# mainboard.net
KiCad netlist of a schematic drawn in EAGLE
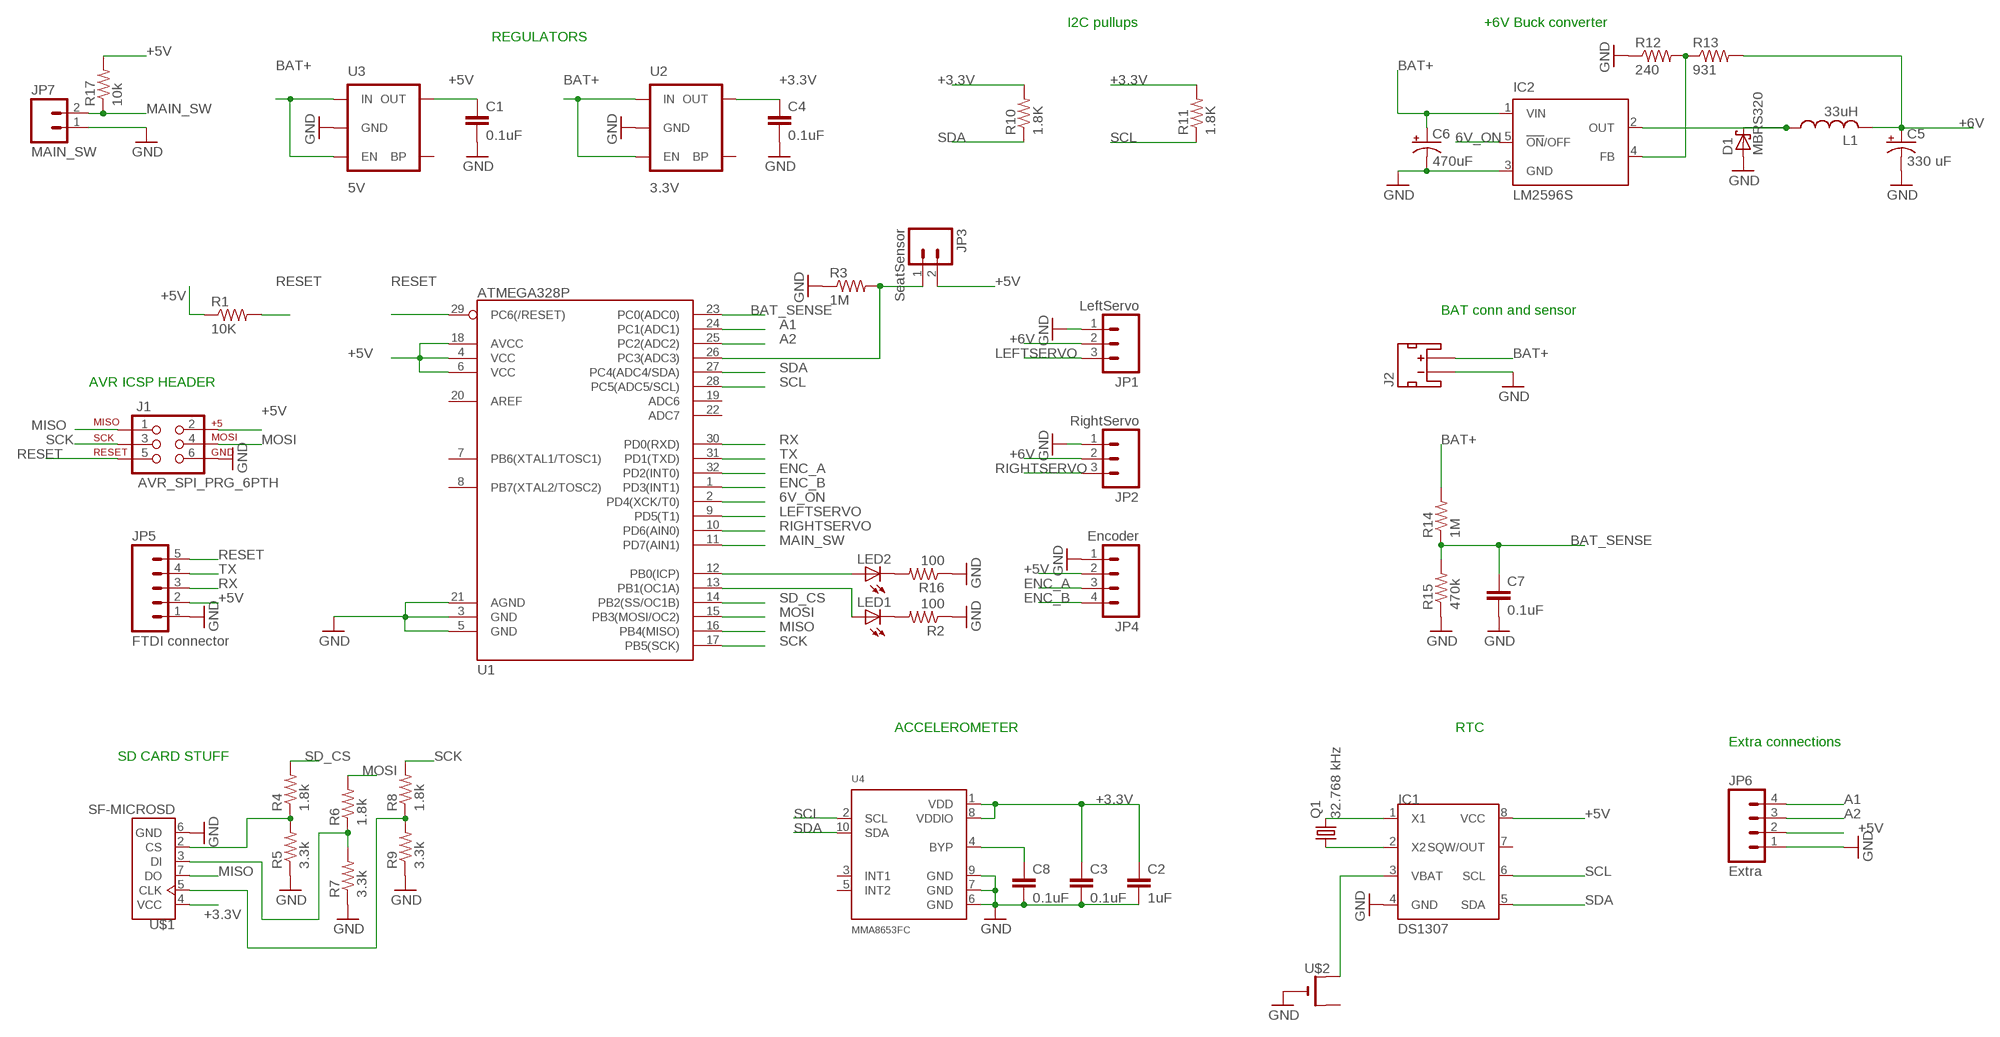
[diagram p0: schematic, sheet 1]

(export (version "E")
  (design (tool "Eeschema 10.0.6"))
  (components
    (comp (ref "C1")
      (value "0.1uF")
      (footprint "eagle-import:0603-CAP")
      (libsource (lib "eagle-import") (part "CAP0603-CAP"))
    )
    (comp (ref "C2")
      (value "1uF")
      (footprint "eagle-import:0603-CAP")
      (libsource (lib "eagle-import") (part "CAP0603-CAP"))
    )
    (comp (ref "C3")
      (value "0.1uF")
      (footprint "eagle-import:0603-CAP")
      (libsource (lib "eagle-import") (part "CAP0603-CAP"))
    )
    (comp (ref "C4")
      (value "0.1uF")
      (footprint "eagle-import:0603-CAP")
      (libsource (lib "eagle-import") (part "CAP0603-CAP"))
    )
    (comp (ref "C5")
      (value "330 uF")
      (footprint "eagle-import:PANASONIC_E")
      (libsource (lib "eagle-import") (part "CAP_POLE"))
    )
    (comp (ref "C6")
      (value "470uF")
      (footprint "eagle-import:PANASONIC_G")
      (libsource (lib "eagle-import") (part "CAP_POLG"))
    )
    (comp (ref "C7")
      (value "0.1uF")
      (footprint "eagle-import:0603-CAP")
      (libsource (lib "eagle-import") (part "CAP0603-CAP"))
    )
    (comp (ref "C8")
      (value "0.1uF")
      (footprint "eagle-import:0603-CAP")
      (libsource (lib "eagle-import") (part "CAP0603-CAP"))
    )
    (comp (ref "D1")
      (value "MBRS320")
      (footprint "eagle-import:SMC")
      (libsource (lib "eagle-import") (part "SCHOTTKY-DIODESMC"))
    )
    (comp (ref "IC1")
      (value "DS1307")
      (footprint "eagle-import:SOIC-8")
      (libsource (lib "eagle-import") (part "DS1307"))
    )
    (comp (ref "IC2")
      (value "LM2596S")
      (footprint "eagle-import:TO263-5")
      (fields (field (name "MF") "NATIONAL SEMICONDUCTOR") (field (name "MPN") "LM2596S-ADJ/NOPB"))
      (libsource (lib "eagle-import") (part "LM2596S"))
    )
    (comp (ref "J1")
      (value "AVR_SPI_PRG_6PTH")
      (footprint "eagle-import:2X3")
      (libsource (lib "eagle-import") (part "AVR_SPI_PRG_6PTH"))
    )
    (comp (ref "J2")
      (value "JST_2MM_MALE")
      (footprint "eagle-import:JST-2-SMD")
      (libsource (lib "eagle-import") (part "JST_2MM_MALE"))
    )
    (comp (ref "JP1")
      (value "LeftServo")
      (footprint "eagle-import:1X03")
      (libsource (lib "eagle-import") (part "M03PTH"))
    )
    (comp (ref "JP2")
      (value "RightServo")
      (footprint "eagle-import:1X03")
      (libsource (lib "eagle-import") (part "M03PTH"))
    )
    (comp (ref "JP3")
      (value "SeatSensor")
      (footprint "eagle-import:1X02")
      (libsource (lib "eagle-import") (part "M02PTH"))
    )
    (comp (ref "JP4")
      (value "Encoder")
      (footprint "eagle-import:1X04")
      (libsource (lib "eagle-import") (part "M04PTH"))
    )
    (comp (ref "JP5")
      (value "FTDI connector")
      (footprint "eagle-import:1X05")
      (libsource (lib "eagle-import") (part "M05PTH"))
    )
    (comp (ref "JP6")
      (value "Extra")
      (footprint "eagle-import:1X04")
      (libsource (lib "eagle-import") (part "M04PTH"))
    )
    (comp (ref "JP7")
      (value "MAIN_SW")
      (footprint "eagle-import:1X02")
      (libsource (lib "eagle-import") (part "M02PTH"))
    )
    (comp (ref "L1")
      (value "33uH")
      (footprint "eagle-import:SRR1280")
      (libsource (lib "eagle-import") (part "L-SRR1280"))
    )
    (comp (ref "LED1")
      (value "LED1206")
      (footprint "eagle-import:LED-1206")
      (libsource (lib "eagle-import") (part "LED1206"))
    )
    (comp (ref "LED2")
      (value "LED1206")
      (footprint "eagle-import:LED-1206")
      (libsource (lib "eagle-import") (part "LED1206"))
    )
    (comp (ref "Q1")
      (value "32.768 kHz")
      (footprint "eagle-import:TC38H")
      (libsource (lib "eagle-import") (part "CRYSTALTC38H"))
    )
    (comp (ref "R1")
      (value "10K")
      (footprint "eagle-import:0603-RES")
      (libsource (lib "eagle-import") (part "RESISTOR0603-RES"))
    )
    (comp (ref "R2")
      (value "100")
      (footprint "eagle-import:0603-RES")
      (libsource (lib "eagle-import") (part "RESISTOR0603-RES"))
    )
    (comp (ref "R3")
      (value "1M")
      (footprint "eagle-import:0603-RES")
      (libsource (lib "eagle-import") (part "RESISTOR0603-RES"))
    )
    (comp (ref "R4")
      (value "1.8k")
      (footprint "eagle-import:0603-RES")
      (libsource (lib "eagle-import") (part "RESISTOR0603"))
    )
    (comp (ref "R5")
      (value "3.3k")
      (footprint "eagle-import:0603-RES")
      (libsource (lib "eagle-import") (part "RESISTOR0603"))
    )
    (comp (ref "R6")
      (value "1.8k")
      (footprint "eagle-import:0603-RES")
      (libsource (lib "eagle-import") (part "RESISTOR0603"))
    )
    (comp (ref "R7")
      (value "3.3k")
      (footprint "eagle-import:0603-RES")
      (libsource (lib "eagle-import") (part "RESISTOR0603"))
    )
    (comp (ref "R8")
      (value "1.8k")
      (footprint "eagle-import:0603-RES")
      (libsource (lib "eagle-import") (part "RESISTOR0603"))
    )
    (comp (ref "R9")
      (value "3.3k")
      (footprint "eagle-import:0603-RES")
      (libsource (lib "eagle-import") (part "RESISTOR0603"))
    )
    (comp (ref "R10")
      (value "1.8K")
      (footprint "eagle-import:0603-RES")
      (libsource (lib "eagle-import") (part "RESISTOR0603-RES"))
    )
    (comp (ref "R11")
      (value "1.8K")
      (footprint "eagle-import:0603-RES")
      (libsource (lib "eagle-import") (part "RESISTOR0603-RES"))
    )
    (comp (ref "R12")
      (value "240")
      (footprint "eagle-import:0603-RES")
      (libsource (lib "eagle-import") (part "RESISTOR0603"))
    )
    (comp (ref "R13")
      (value "931")
      (footprint "eagle-import:0603-RES")
      (libsource (lib "eagle-import") (part "RESISTOR0603"))
    )
    (comp (ref "R14")
      (value "1M")
      (footprint "eagle-import:0603-RES")
      (libsource (lib "eagle-import") (part "RESISTOR0603"))
    )
    (comp (ref "R15")
      (value "470k")
      (footprint "eagle-import:0603-RES")
      (libsource (lib "eagle-import") (part "RESISTOR0603"))
    )
    (comp (ref "R16")
      (value "100")
      (footprint "eagle-import:0603-RES")
      (libsource (lib "eagle-import") (part "RESISTOR0603"))
    )
    (comp (ref "R17")
      (value "10k")
      (footprint "eagle-import:0603-RES")
      (libsource (lib "eagle-import") (part "RESISTOR0603"))
    )
    (comp (ref "U$1")
      (value "SF-MICROSD")
      (footprint "eagle-import:MICROSD")
      (libsource (lib "eagle-import") (part "SF-MICROSD"))
    )
    (comp (ref "U$2")
      (value "CR1220SMT")
      (footprint "eagle-import:CR1220-SMD")
      (libsource (lib "eagle-import") (part "CR1220SMT"))
    )
    (comp (ref "U1")
      (value "ATMEGA328P")
      (footprint "eagle-import:TQFP32-08")
      (libsource (lib "eagle-import") (part "ATMEGA328_SMT"))
    )
    (comp (ref "U2")
      (value "3.3V")
      (footprint "eagle-import:SOT23-5")
      (libsource (lib "eagle-import") (part "MIC52053.3V"))
    )
    (comp (ref "U3")
      (value "5V")
      (footprint "eagle-import:SOT23-5")
      (libsource (lib "eagle-import") (part "MIC52055V"))
    )
    (comp (ref "U4")
      (value "MMA8653FC")
      (footprint "eagle-import:DFN10-2X2")
      (libsource (lib "eagle-import") (part "MMA8653FC"))
    )
  )
  (nets
    (net (code "1") (name "/+3.3V") (class "Default")
      (node (ref "C2") (pin "1") (pinfunction "1_1") (pintype "passive"))
      (node (ref "C3") (pin "1") (pinfunction "1_1") (pintype "passive"))
      (node (ref "C4") (pin "1") (pinfunction "1_1") (pintype "passive"))
      (node (ref "R10") (pin "2") (pinfunction "2_2") (pintype "passive"))
      (node (ref "R11") (pin "2") (pinfunction "2_2") (pintype "passive"))
      (node (ref "U$1") (pin "4") (pinfunction "VCC_4") (pintype "passive"))
      (node (ref "U2") (pin "5") (pinfunction "OUT_5") (pintype "passive"))
      (node (ref "U4") (pin "1") (pinfunction "VDD_1") (pintype "bidirectional"))
      (node (ref "U4") (pin "8") (pinfunction "VDDIO_8") (pintype "bidirectional"))
    )
    (net (code "2") (name "/+5V") (class "Default")
      (node (ref "C1") (pin "1") (pinfunction "1_1") (pintype "passive"))
      (node (ref "IC1") (pin "8") (pinfunction "VCC_8") (pintype "power_in"))
      (node (ref "J1") (pin "2") (pinfunction "2_2") (pintype "passive"))
      (node (ref "JP3") (pin "2") (pinfunction "2_2") (pintype "passive"))
      (node (ref "JP4") (pin "2") (pinfunction "2_2") (pintype "passive"))
      (node (ref "JP5") (pin "2") (pinfunction "2_2") (pintype "passive"))
      (node (ref "JP6") (pin "2") (pinfunction "2_2") (pintype "passive"))
      (node (ref "R1") (pin "1") (pinfunction "1_1") (pintype "passive"))
      (node (ref "R17") (pin "2") (pinfunction "2_2") (pintype "passive"))
      (node (ref "U1") (pin "18") (pinfunction "AVCC_18") (pintype "bidirectional"))
      (node (ref "U1") (pin "4") (pinfunction "VCC_4") (pintype "bidirectional"))
      (node (ref "U1") (pin "6") (pinfunction "VCC_6") (pintype "bidirectional"))
      (node (ref "U3") (pin "5") (pinfunction "OUT_5") (pintype "passive"))
    )
    (net (code "3") (name "/+6V") (class "Default")
      (node (ref "C5") (pin "+") (pinfunction "+_+") (pintype "passive"))
      (node (ref "JP1") (pin "2") (pinfunction "2_2") (pintype "passive"))
      (node (ref "JP2") (pin "2") (pinfunction "2_2") (pintype "passive"))
      (node (ref "L1") (pin "2") (pinfunction "2_2") (pintype "passive"))
      (node (ref "R13") (pin "2") (pinfunction "2_2") (pintype "passive"))
    )
    (net (code "4") (name "/6V_ON") (class "Default")
      (node (ref "IC2") (pin "5") (pinfunction "~{ON}/OFF_5") (pintype "input"))
      (node (ref "U1") (pin "2") (pinfunction "PD4(XCK/T0)_2") (pintype "bidirectional"))
    )
    (net (code "5") (name "/A1") (class "Default")
      (node (ref "JP6") (pin "4") (pinfunction "4_4") (pintype "passive"))
      (node (ref "U1") (pin "24") (pinfunction "PC1(ADC1)_24") (pintype "bidirectional"))
    )
    (net (code "6") (name "/A2") (class "Default")
      (node (ref "JP6") (pin "3") (pinfunction "3_3") (pintype "passive"))
      (node (ref "U1") (pin "25") (pinfunction "PC2(ADC2)_25") (pintype "bidirectional"))
    )
    (net (code "7") (name "/BAT+") (class "Default")
      (node (ref "C6") (pin "+") (pinfunction "+_+") (pintype "passive"))
      (node (ref "IC2") (pin "1") (pinfunction "VIN_1") (pintype "input"))
      (node (ref "J2") (pin "2") (pinfunction "+_2") (pintype "bidirectional"))
      (node (ref "R14") (pin "2") (pinfunction "2_2") (pintype "passive"))
      (node (ref "U2") (pin "1") (pinfunction "IN_1") (pintype "input"))
      (node (ref "U2") (pin "3") (pinfunction "EN_3") (pintype "input"))
      (node (ref "U3") (pin "1") (pinfunction "IN_1") (pintype "input"))
      (node (ref "U3") (pin "3") (pinfunction "EN_3") (pintype "input"))
    )
    (net (code "8") (name "/BAT_SENSE") (class "Default")
      (node (ref "C7") (pin "1") (pinfunction "1_1") (pintype "passive"))
      (node (ref "R14") (pin "1") (pinfunction "1_1") (pintype "passive"))
      (node (ref "R15") (pin "2") (pinfunction "2_2") (pintype "passive"))
      (node (ref "U1") (pin "23") (pinfunction "PC0(ADC0)_23") (pintype "bidirectional"))
    )
    (net (code "9") (name "/ENC_A") (class "Default")
      (node (ref "JP4") (pin "3") (pinfunction "3_3") (pintype "passive"))
      (node (ref "U1") (pin "32") (pinfunction "PD2(INT0)_32") (pintype "bidirectional"))
    )
    (net (code "10") (name "/ENC_B") (class "Default")
      (node (ref "JP4") (pin "4") (pinfunction "4_4") (pintype "passive"))
      (node (ref "U1") (pin "1") (pinfunction "PD3(INT1)_1") (pintype "bidirectional"))
    )
    (net (code "11") (name "/LEFTSERVO") (class "Default")
      (node (ref "JP1") (pin "3") (pinfunction "3_3") (pintype "passive"))
      (node (ref "U1") (pin "9") (pinfunction "PD5(T1)_9") (pintype "bidirectional"))
    )
    (net (code "12") (name "/MAIN_SW") (class "Default")
      (node (ref "JP7") (pin "2") (pinfunction "2_2") (pintype "passive"))
      (node (ref "R17") (pin "1") (pinfunction "1_1") (pintype "passive"))
      (node (ref "U1") (pin "11") (pinfunction "PD7(AIN1)_11") (pintype "bidirectional"))
    )
    (net (code "13") (name "/MISO") (class "Default")
      (node (ref "J1") (pin "1") (pinfunction "1_1") (pintype "passive"))
      (node (ref "U$1") (pin "7") (pinfunction "DO_7") (pintype "bidirectional"))
      (node (ref "U1") (pin "16") (pinfunction "PB4(MISO)_16") (pintype "bidirectional"))
    )
    (net (code "14") (name "/MOSI") (class "Default")
      (node (ref "J1") (pin "4") (pinfunction "4_4") (pintype "passive"))
      (node (ref "R6") (pin "2") (pinfunction "2_2") (pintype "passive"))
      (node (ref "U1") (pin "15") (pinfunction "PB3(MOSI/OC2)_15") (pintype "bidirectional"))
    )
    (net (code "15") (name "/RESET") (class "Default")
      (node (ref "J1") (pin "5") (pinfunction "5_5") (pintype "passive"))
      (node (ref "JP5") (pin "5") (pinfunction "5_5") (pintype "passive"))
      (node (ref "R1") (pin "2") (pinfunction "2_2") (pintype "passive"))
      (node (ref "U1") (pin "29") (pinfunction "PC6(/RESET)_29") (pintype "bidirectional"))
    )
    (net (code "16") (name "/RIGHTSERVO") (class "Default")
      (node (ref "JP2") (pin "3") (pinfunction "3_3") (pintype "passive"))
      (node (ref "U1") (pin "10") (pinfunction "PD6(AIN0)_10") (pintype "bidirectional"))
    )
    (net (code "17") (name "/RX") (class "Default")
      (node (ref "JP5") (pin "3") (pinfunction "3_3") (pintype "passive"))
      (node (ref "U1") (pin "30") (pinfunction "PD0(RXD)_30") (pintype "bidirectional"))
    )
    (net (code "18") (name "/SCK") (class "Default")
      (node (ref "J1") (pin "3") (pinfunction "3_3") (pintype "passive"))
      (node (ref "R8") (pin "2") (pinfunction "2_2") (pintype "passive"))
      (node (ref "U1") (pin "17") (pinfunction "PB5(SCK)_17") (pintype "bidirectional"))
    )
    (net (code "19") (name "/SCL") (class "Default")
      (node (ref "IC1") (pin "6") (pinfunction "SCL_6") (pintype "input"))
      (node (ref "R11") (pin "1") (pinfunction "1_1") (pintype "passive"))
      (node (ref "U1") (pin "28") (pinfunction "PC5(ADC5/SCL)_28") (pintype "bidirectional"))
      (node (ref "U4") (pin "2") (pinfunction "SCL_2") (pintype "bidirectional"))
    )
    (net (code "20") (name "/SDA") (class "Default")
      (node (ref "IC1") (pin "5") (pinfunction "SDA_5") (pintype "bidirectional"))
      (node (ref "R10") (pin "1") (pinfunction "1_1") (pintype "passive"))
      (node (ref "U1") (pin "27") (pinfunction "PC4(ADC4/SDA)_27") (pintype "bidirectional"))
      (node (ref "U4") (pin "10") (pinfunction "SDA_10") (pintype "bidirectional"))
    )
    (net (code "21") (name "/SD_CS") (class "Default")
      (node (ref "R4") (pin "2") (pinfunction "2_2") (pintype "passive"))
      (node (ref "U1") (pin "14") (pinfunction "PB2(SS/OC1B)_14") (pintype "bidirectional"))
    )
    (net (code "22") (name "/TX") (class "Default")
      (node (ref "JP5") (pin "4") (pinfunction "4_4") (pintype "passive"))
      (node (ref "U1") (pin "31") (pinfunction "PD1(TXD)_31") (pintype "bidirectional"))
    )
    (net (code "23") (name "GND") (class "Default")
      (node (ref "C1") (pin "2") (pinfunction "2_2") (pintype "passive"))
      (node (ref "C2") (pin "2") (pinfunction "2_2") (pintype "passive"))
      (node (ref "C3") (pin "2") (pinfunction "2_2") (pintype "passive"))
      (node (ref "C4") (pin "2") (pinfunction "2_2") (pintype "passive"))
      (node (ref "C5") (pin "-") (pinfunction "-_-") (pintype "passive"))
      (node (ref "C6") (pin "-") (pinfunction "-_-") (pintype "passive"))
      (node (ref "C7") (pin "2") (pinfunction "2_2") (pintype "passive"))
      (node (ref "C8") (pin "2") (pinfunction "2_2") (pintype "passive"))
      (node (ref "D1") (pin "A") (pinfunction "A_A") (pintype "passive"))
      (node (ref "IC1") (pin "4") (pinfunction "GND_4") (pintype "power_in"))
      (node (ref "IC2") (pin "3") (pinfunction "GND_3") (pintype "power_in"))
      (node (ref "J1") (pin "6") (pinfunction "6_6") (pintype "passive"))
      (node (ref "J2") (pin "1") (pinfunction "-_1") (pintype "bidirectional"))
      (node (ref "JP1") (pin "1") (pinfunction "1_1") (pintype "passive"))
      (node (ref "JP2") (pin "1") (pinfunction "1_1") (pintype "passive"))
      (node (ref "JP4") (pin "1") (pinfunction "1_1") (pintype "passive"))
      (node (ref "JP5") (pin "1") (pinfunction "1_1") (pintype "passive"))
      (node (ref "JP6") (pin "1") (pinfunction "1_1") (pintype "passive"))
      (node (ref "JP7") (pin "1") (pinfunction "1_1") (pintype "passive"))
      (node (ref "R12") (pin "1") (pinfunction "1_1") (pintype "passive"))
      (node (ref "R15") (pin "1") (pinfunction "1_1") (pintype "passive"))
      (node (ref "R16") (pin "1") (pinfunction "1_1") (pintype "passive"))
      (node (ref "R2") (pin "1") (pinfunction "1_1") (pintype "passive"))
      (node (ref "R3") (pin "1") (pinfunction "1_1") (pintype "passive"))
      (node (ref "R5") (pin "1") (pinfunction "1_1") (pintype "passive"))
      (node (ref "R7") (pin "1") (pinfunction "1_1") (pintype "passive"))
      (node (ref "R9") (pin "1") (pinfunction "1_1") (pintype "passive"))
      (node (ref "U$1") (pin "6") (pinfunction "GND_6") (pintype "power_in"))
      (node (ref "U$2") (pin "-") (pinfunction "-_-") (pintype "passive"))
      (node (ref "U1") (pin "21") (pinfunction "AGND_21") (pintype "bidirectional"))
      (node (ref "U1") (pin "3") (pinfunction "GND_3") (pintype "bidirectional"))
      (node (ref "U1") (pin "5") (pinfunction "GND_5") (pintype "bidirectional"))
      (node (ref "U2") (pin "2") (pinfunction "GND_2") (pintype "input"))
      (node (ref "U3") (pin "2") (pinfunction "GND_2") (pintype "input"))
      (node (ref "U4") (pin "6") (pinfunction "GND_6") (pintype "bidirectional"))
      (node (ref "U4") (pin "7") (pinfunction "GND_7") (pintype "bidirectional"))
      (node (ref "U4") (pin "9") (pinfunction "GND_9") (pintype "bidirectional"))
    )
    (net (code "24") (name "Net-(IC1-VBAT)") (class "Default")
      (node (ref "IC1") (pin "3") (pinfunction "VBAT_3") (pintype "power_in"))
      (node (ref "U$2") (pin "+$1") (pinfunction "+_+$1") (pintype "passive"))
    )
    (net (code "25") (name "Net-(IC1-X1)") (class "Default")
      (node (ref "IC1") (pin "1") (pinfunction "X1_1") (pintype "input"))
      (node (ref "Q1") (pin "2") (pinfunction "2_2") (pintype "passive"))
    )
    (net (code "26") (name "Net-(IC1-X2)") (class "Default")
      (node (ref "IC1") (pin "2") (pinfunction "X2_2") (pintype "output"))
      (node (ref "Q1") (pin "1") (pinfunction "1_1") (pintype "passive"))
    )
    (net (code "27") (name "Net-(IC2-FB)") (class "Default")
      (node (ref "IC2") (pin "4") (pinfunction "FB_4") (pintype "input"))
      (node (ref "R12") (pin "2") (pinfunction "2_2") (pintype "passive"))
      (node (ref "R13") (pin "1") (pinfunction "1_1") (pintype "passive"))
    )
    (net (code "28") (name "Net-(IC2-OUT)") (class "Default")
      (node (ref "D1") (pin "C") (pinfunction "C_C") (pintype "passive"))
      (node (ref "IC2") (pin "2") (pinfunction "OUT_2") (pintype "output"))
      (node (ref "L1") (pin "1") (pinfunction "1_1") (pintype "passive"))
    )
    (net (code "29") (name "Net-(LED1-PadC)") (class "Default")
      (node (ref "LED1") (pin "C") (pinfunction "C_C") (pintype "passive"))
      (node (ref "R2") (pin "2") (pinfunction "2_2") (pintype "passive"))
    )
    (net (code "30") (name "Net-(LED2-PadC)") (class "Default")
      (node (ref "LED2") (pin "C") (pinfunction "C_C") (pintype "passive"))
      (node (ref "R16") (pin "2") (pinfunction "2_2") (pintype "passive"))
    )
    (net (code "31") (name "Net-(U$1-CLK)") (class "Default")
      (node (ref "R8") (pin "1") (pinfunction "1_1") (pintype "passive"))
      (node (ref "R9") (pin "2") (pinfunction "2_2") (pintype "passive"))
      (node (ref "U$1") (pin "5") (pinfunction "CLK_5") (pintype "bidirectional"))
    )
    (net (code "32") (name "Net-(U$1-CS)") (class "Default")
      (node (ref "R4") (pin "1") (pinfunction "1_1") (pintype "passive"))
      (node (ref "R5") (pin "2") (pinfunction "2_2") (pintype "passive"))
      (node (ref "U$1") (pin "2") (pinfunction "CS_2") (pintype "bidirectional"))
    )
    (net (code "33") (name "Net-(U$1-DI)") (class "Default")
      (node (ref "R6") (pin "1") (pinfunction "1_1") (pintype "passive"))
      (node (ref "R7") (pin "2") (pinfunction "2_2") (pintype "passive"))
      (node (ref "U$1") (pin "3") (pinfunction "DI_3") (pintype "bidirectional"))
    )
    (net (code "34") (name "Net-(U1-PB0(ICP))") (class "Default")
      (node (ref "LED2") (pin "A") (pinfunction "A_A") (pintype "passive"))
      (node (ref "U1") (pin "12") (pinfunction "PB0(ICP)_12") (pintype "bidirectional"))
    )
    (net (code "35") (name "Net-(U1-PB1(OC1A))") (class "Default")
      (node (ref "LED1") (pin "A") (pinfunction "A_A") (pintype "passive"))
      (node (ref "U1") (pin "13") (pinfunction "PB1(OC1A)_13") (pintype "bidirectional"))
    )
    (net (code "36") (name "Net-(U1-PC3(ADC3))") (class "Default")
      (node (ref "JP3") (pin "1") (pinfunction "1_1") (pintype "passive"))
      (node (ref "R3") (pin "2") (pinfunction "2_2") (pintype "passive"))
      (node (ref "U1") (pin "26") (pinfunction "PC3(ADC3)_26") (pintype "bidirectional"))
    )
    (net (code "37") (name "Net-(U4-BYP)") (class "Default")
      (node (ref "C8") (pin "1") (pinfunction "1_1") (pintype "passive"))
      (node (ref "U4") (pin "4") (pinfunction "BYP_4") (pintype "bidirectional"))
    )
    (net (code "38") (name "unconnected-(IC1-SQW{slash}OUT-Pad7)") (class "Default")
      (node (ref "IC1") (pin "7") (pinfunction "SQW/OUT_7") (pintype "output"))
    )
    (net (code "39") (name "unconnected-(J2-PAD1-PadNC1)") (class "Default")
      (node (ref "J2") (pin "NC1") (pinfunction "PAD1_NC1") (pintype "bidirectional"))
    )
    (net (code "40") (name "unconnected-(J2-PAD2-PadNC2)") (class "Default")
      (node (ref "J2") (pin "NC2") (pinfunction "PAD2_NC2") (pintype "bidirectional"))
    )
    (net (code "41") (name "unconnected-(U$2-+1-Pad+$2)") (class "Default")
      (node (ref "U$2") (pin "+$2") (pinfunction "+1_+$2") (pintype "passive"))
    )
    (net (code "42") (name "unconnected-(U1-ADC6-Pad19)") (class "Default")
      (node (ref "U1") (pin "19") (pinfunction "ADC6_19") (pintype "bidirectional"))
    )
    (net (code "43") (name "unconnected-(U1-ADC7-Pad22)") (class "Default")
      (node (ref "U1") (pin "22") (pinfunction "ADC7_22") (pintype "bidirectional"))
    )
    (net (code "44") (name "unconnected-(U1-AREF-Pad20)") (class "Default")
      (node (ref "U1") (pin "20") (pinfunction "AREF_20") (pintype "bidirectional"))
    )
    (net (code "45") (name "unconnected-(U1-PB6(XTAL1{slash}TOSC1)-Pad7)") (class "Default")
      (node (ref "U1") (pin "7") (pinfunction "PB6(XTAL1/TOSC1)_7") (pintype "bidirectional"))
    )
    (net (code "46") (name "unconnected-(U1-PB7(XTAL2{slash}TOSC2)-Pad8)") (class "Default")
      (node (ref "U1") (pin "8") (pinfunction "PB7(XTAL2/TOSC2)_8") (pintype "bidirectional"))
    )
    (net (code "47") (name "unconnected-(U2-BP-Pad4)") (class "Default")
      (node (ref "U2") (pin "4") (pinfunction "BP_4") (pintype "input"))
    )
    (net (code "48") (name "unconnected-(U3-BP-Pad4)") (class "Default")
      (node (ref "U3") (pin "4") (pinfunction "BP_4") (pintype "input"))
    )
    (net (code "49") (name "unconnected-(U4-INT1-Pad3)") (class "Default")
      (node (ref "U4") (pin "3") (pinfunction "INT1_3") (pintype "bidirectional"))
    )
    (net (code "50") (name "unconnected-(U4-INT2-Pad5)") (class "Default")
      (node (ref "U4") (pin "5") (pinfunction "INT2_5") (pintype "bidirectional"))
    )
  )
)
